# POWER_INPUT_STAGE.net
KiCad netlist of a schematic drawn in Altium Designer
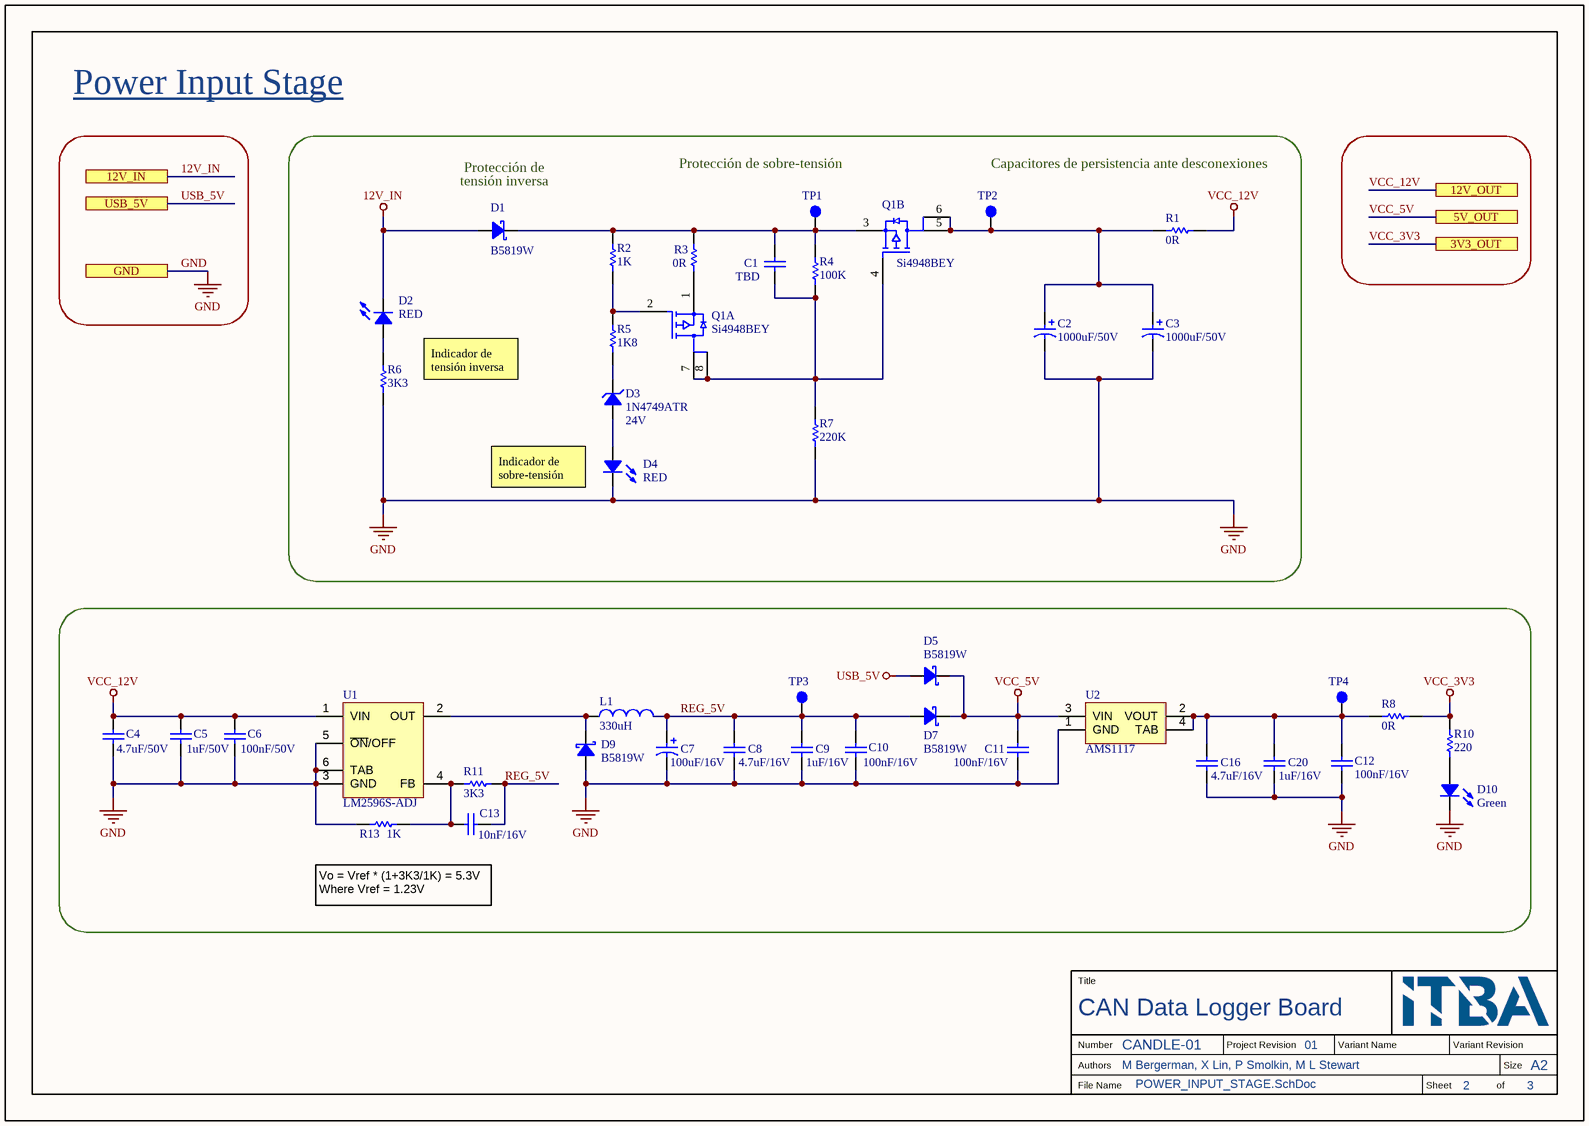
[diagram p0: POWER_INPUT_STAGE.SchDoc]

(export (version "E")
  (design (tool "Eeschema 10.0.6"))
  (components
    (comp (ref "C1")
      (value "TBD")
      (footprint "CAP0805")
      (description "SMD 0805 Capacitor")
      (libsource (lib "CANDLE-LIB") (part "Capacitor"))
    )
    (comp (ref "C2")
      (value "1000uF/50V")
      (footprint "RAD-CAP-12.5/5mm")
      (description "Polarized Capacitor (Radial)")
      (libsource (lib "CANDLE-LIB") (part "Capacitor Polarized"))
    )
    (comp (ref "C3")
      (value "1000uF/50V")
      (footprint "RAD-CAP-12.5/5mm")
      (description "Polarized Capacitor (Radial)")
      (libsource (lib "CANDLE-LIB") (part "Capacitor Polarized"))
    )
    (comp (ref "C4")
      (value "4.7uF/50V")
      (footprint "CAP0805")
      (description "SMD 0805 Capacitor")
      (libsource (lib "CANDLE-LIB") (part "Capacitor"))
    )
    (comp (ref "C5")
      (value "1uF/50V")
      (footprint "CAP0805")
      (description "SMD 0805 Capacitor")
      (libsource (lib "CANDLE-LIB") (part "Capacitor"))
    )
    (comp (ref "C6")
      (value "100nF/50V")
      (footprint "CAP0805")
      (description "SMD 0805 Capacitor")
      (libsource (lib "CANDLE-LIB") (part "Capacitor"))
    )
    (comp (ref "C7")
      (value "100uF/16V")
      (footprint "RAD-CAP-12.5/5mm")
      (description "Polarized Capacitor (Radial)")
      (libsource (lib "CANDLE-LIB") (part "Capacitor Polarized"))
    )
    (comp (ref "C8")
      (value "4.7uF/16V")
      (footprint "CAP0805")
      (description "SMD 0805 Capacitor")
      (libsource (lib "CANDLE-LIB") (part "Capacitor"))
    )
    (comp (ref "C9")
      (value "1uF/16V")
      (footprint "CAP0805")
      (description "SMD 0805 Capacitor")
      (libsource (lib "CANDLE-LIB") (part "Capacitor"))
    )
    (comp (ref "C10")
      (value "100nF/16V")
      (footprint "CAP0805")
      (description "SMD 0805 Capacitor")
      (libsource (lib "CANDLE-LIB") (part "Capacitor"))
    )
    (comp (ref "C11")
      (value "100nF/16V")
      (footprint "CAP0805")
      (description "SMD 0805 Capacitor")
      (libsource (lib "CANDLE-LIB") (part "Capacitor"))
    )
    (comp (ref "C12")
      (value "100nF/16V")
      (footprint "CAP0805")
      (description "SMD 0805 Capacitor")
      (libsource (lib "CANDLE-LIB") (part "Capacitor"))
    )
    (comp (ref "C13")
      (value "10nF/16V")
      (footprint "CAP0805")
      (description "SMD 0805 Capacitor")
      (libsource (lib "CANDLE-LIB") (part "Capacitor"))
    )
    (comp (ref "C16")
      (value "4.7uF/16V")
      (footprint "CAP0805")
      (description "SMD 0805 Capacitor")
      (libsource (lib "CANDLE-LIB") (part "Capacitor"))
    )
    (comp (ref "C20")
      (value "1uF/16V")
      (footprint "CAP0805")
      (description "SMD 0805 Capacitor")
      (libsource (lib "CANDLE-LIB") (part "Capacitor"))
    )
    (comp (ref "D1")
      (value "B5819W")
      (footprint "SOD-123")
      (description "Schottky Diode")
      (libsource (lib "CANDLE-LIB") (part "Diode Schottky"))
    )
    (comp (ref "D2")
      (value "RED")
      (footprint "LED-3MM-RED-RA")
      (description "Red 3mm LED")
      (libsource (lib "CANDLE-LIB") (part "LED 3mm Red RA"))
    )
    (comp (ref "D3")
      (value "1N4749ATR")
      (footprint "DO-35")
      (description "Zener Diode")
      (fields (field (name "VOLTAGE") "24V"))
      (libsource (lib "CANDLE-LIB") (part "Diode Zener"))
    )
    (comp (ref "D4")
      (value "RED")
      (footprint "LED-3MM-RED-RA")
      (description "Red 3mm LED")
      (libsource (lib "CANDLE-LIB") (part "LED 3mm Red RA"))
    )
    (comp (ref "D5")
      (value "B5819W")
      (footprint "SOD-123")
      (description "Schottky Diode")
      (libsource (lib "CANDLE-LIB") (part "Diode Schottky"))
    )
    (comp (ref "D7")
      (value "B5819W")
      (footprint "SOD-123")
      (description "Schottky Diode")
      (libsource (lib "CANDLE-LIB") (part "Diode Schottky"))
    )
    (comp (ref "D9")
      (value "B5819W")
      (footprint "SOD-123")
      (description "Schottky Diode")
      (libsource (lib "CANDLE-LIB") (part "Diode Schottky"))
    )
    (comp (ref "D10")
      (value "Green")
      (footprint "LED-3MM-GREEN-RA")
      (description "Green 3mm LED")
      (libsource (lib "CANDLE-LIB") (part "LED 3mm Green RA"))
    )
    (comp (ref "L1")
      (value "330uH")
      (footprint "DRQ127-INDUCTOR")
      (description "Inductor")
      (fields (field (name "PUBLISHER") "Altium Limited"))
      (libsource (lib "CANDLE-LIB") (part "Inductor"))
    )
    (comp (ref "Q1")
      (value "Si4948BEY")
      (footprint "8-SOIC")
      (description "MOSFET 2P-CH 60V 2.4A 8-SOIC")
      (libsource (lib "CANDLE-LIB") (part "Si4948BEY"))
    )
    (comp (ref "R1")
      (value "0R")
      (footprint "RES0805")
      (description "SMD 0805 Resistor")
      (libsource (lib "CANDLE-LIB") (part "Resistor"))
    )
    (comp (ref "R2")
      (value "1K")
      (footprint "RES0805")
      (description "SMD 0805 Resistor")
      (libsource (lib "CANDLE-LIB") (part "Resistor"))
    )
    (comp (ref "R3")
      (value "0R")
      (footprint "RES0805")
      (description "SMD 0805 Resistor")
      (libsource (lib "CANDLE-LIB") (part "Resistor"))
    )
    (comp (ref "R4")
      (value "100K")
      (footprint "RES0805")
      (description "SMD 0805 Resistor")
      (libsource (lib "CANDLE-LIB") (part "Resistor"))
    )
    (comp (ref "R5")
      (value "1K8")
      (footprint "RES0805")
      (description "SMD 0805 Resistor")
      (libsource (lib "CANDLE-LIB") (part "Resistor"))
    )
    (comp (ref "R6")
      (value "3K3")
      (footprint "RES0805")
      (description "SMD 0805 Resistor")
      (libsource (lib "CANDLE-LIB") (part "Resistor"))
    )
    (comp (ref "R7")
      (value "220K")
      (footprint "RES0805")
      (description "SMD 0805 Resistor")
      (libsource (lib "CANDLE-LIB") (part "Resistor"))
    )
    (comp (ref "R8")
      (value "0R")
      (footprint "RES0805")
      (description "SMD 0805 Resistor")
      (libsource (lib "CANDLE-LIB") (part "Resistor"))
    )
    (comp (ref "R10")
      (value "220")
      (footprint "RES0805")
      (description "SMD 0805 Resistor")
      (libsource (lib "CANDLE-LIB") (part "Resistor"))
    )
    (comp (ref "R11")
      (value "3K3")
      (footprint "RES0805")
      (description "SMD 0805 Resistor")
      (libsource (lib "CANDLE-LIB") (part "Resistor"))
    )
    (comp (ref "R13")
      (value "1K")
      (footprint "RES0805")
      (description "SMD 0805 Resistor")
      (libsource (lib "CANDLE-LIB") (part "Resistor"))
    )
    (comp (ref "TP1")
      (value "Testpoint")
      (footprint "TP_SMD_Ø1.0mm")
      (libsource (lib "CANDLE-LIB") (part "Testpoint"))
    )
    (comp (ref "TP2")
      (value "Testpoint")
      (footprint "TP_SMD_Ø1.0mm")
      (libsource (lib "CANDLE-LIB") (part "Testpoint"))
    )
    (comp (ref "TP3")
      (value "Testpoint")
      (footprint "TP_SMD_Ø1.0mm")
      (libsource (lib "CANDLE-LIB") (part "Testpoint"))
    )
    (comp (ref "TP4")
      (value "Testpoint")
      (footprint "TP_SMD_Ø1.0mm")
      (libsource (lib "CANDLE-LIB") (part "Testpoint"))
    )
    (comp (ref "U1")
      (value "LM2596S-ADJ")
      (footprint "LM2596S-ADJ/NOPB")
      (description "SIMPLE SWITCHER® Power Converter 150 KHz 3A Step-Down Voltage Regulator, 5-pin TO-263, Pb-Free")
      (libsource (lib "CANDLE-LIB") (part "LM2596S-ADJ/NOPB"))
    )
    (comp (ref "U2")
      (value "AMS1117")
      (footprint "SOT223")
      (description "1A LOW DROPOUT VOLTAGE REGULATOR")
      (libsource (lib "CANDLE-LIB") (part "AMS1117"))
    )
  )
  (nets
    (net (code "1") (name "/REG_5V") (class "Default")
      (node (ref "C10") (pin "2") (pinfunction "2_2") (pintype "passive"))
      (node (ref "C13") (pin "2") (pinfunction "2_2") (pintype "passive"))
      (node (ref "C7") (pin "2") (pinfunction "2_2") (pintype "passive"))
      (node (ref "C8") (pin "2") (pinfunction "2_2") (pintype "passive"))
      (node (ref "C9") (pin "2") (pinfunction "2_2") (pintype "passive"))
      (node (ref "D7") (pin "1") (pinfunction "A_1") (pintype "passive"))
      (node (ref "L1") (pin "2") (pinfunction "2_2") (pintype "passive"))
      (node (ref "R11") (pin "1") (pinfunction "1_1") (pintype "passive"))
      (node (ref "TP3") (pin "1") (pinfunction "TP_1") (pintype "passive"))
    )
    (net (code "2") (name "12V_IN") (class "Default")
      (node (ref "D1") (pin "1") (pinfunction "A_1") (pintype "passive"))
      (node (ref "D2") (pin "2") (pinfunction "K_2") (pintype "passive"))
    )
    (net (code "3") (name "GND") (class "Default")
      (node (ref "C10") (pin "1") (pinfunction "1_1") (pintype "passive"))
      (node (ref "C11") (pin "1") (pinfunction "1_1") (pintype "passive"))
      (node (ref "C12") (pin "1") (pinfunction "1_1") (pintype "passive"))
      (node (ref "C16") (pin "1") (pinfunction "1_1") (pintype "passive"))
      (node (ref "C2") (pin "1") (pinfunction "1_1") (pintype "passive"))
      (node (ref "C20") (pin "1") (pinfunction "1_1") (pintype "passive"))
      (node (ref "C3") (pin "1") (pinfunction "1_1") (pintype "passive"))
      (node (ref "C4") (pin "1") (pinfunction "1_1") (pintype "passive"))
      (node (ref "C5") (pin "1") (pinfunction "1_1") (pintype "passive"))
      (node (ref "C6") (pin "1") (pinfunction "1_1") (pintype "passive"))
      (node (ref "C7") (pin "1") (pinfunction "1_1") (pintype "passive"))
      (node (ref "C8") (pin "1") (pinfunction "1_1") (pintype "passive"))
      (node (ref "C9") (pin "1") (pinfunction "1_1") (pintype "passive"))
      (node (ref "D10") (pin "2") (pinfunction "K_2") (pintype "passive"))
      (node (ref "D4") (pin "2") (pinfunction "K_2") (pintype "passive"))
      (node (ref "D9") (pin "1") (pinfunction "A_1") (pintype "passive"))
      (node (ref "R13") (pin "2") (pinfunction "2_2") (pintype "passive"))
      (node (ref "R6") (pin "1") (pinfunction "1_1") (pintype "passive"))
      (node (ref "R7") (pin "1") (pinfunction "1_1") (pintype "passive"))
      (node (ref "U1") (pin "3") (pinfunction "GND_3") (pintype "power_in"))
      (node (ref "U1") (pin "5") (pinfunction "~{ON}/OFF_5") (pintype "passive"))
      (node (ref "U1") (pin "6") (pinfunction "TAB_6") (pintype "passive"))
      (node (ref "U2") (pin "1") (pinfunction "GND_1") (pintype "passive"))
    )
    (net (code "4") (name "Net-(D1-K)") (class "Default")
      (node (ref "C1") (pin "2") (pinfunction "2_2") (pintype "passive"))
      (node (ref "D1") (pin "2") (pinfunction "K_2") (pintype "passive"))
      (node (ref "Q1") (pin "3") (pinfunction "S2_3") (pintype "passive"))
      (node (ref "R2") (pin "2") (pinfunction "2_2") (pintype "passive"))
      (node (ref "R3") (pin "2") (pinfunction "2_2") (pintype "passive"))
      (node (ref "R4") (pin "2") (pinfunction "2_2") (pintype "passive"))
      (node (ref "TP1") (pin "1") (pinfunction "TP_1") (pintype "passive"))
    )
    (net (code "5") (name "Net-(D2-A)") (class "Default")
      (node (ref "D2") (pin "1") (pinfunction "A_1") (pintype "passive"))
      (node (ref "R6") (pin "2") (pinfunction "2_2") (pintype "passive"))
    )
    (net (code "6") (name "Net-(D3-A)") (class "Default")
      (node (ref "D3") (pin "2") (pinfunction "A_2") (pintype "passive"))
      (node (ref "D4") (pin "1") (pinfunction "A_1") (pintype "passive"))
    )
    (net (code "7") (name "Net-(D3-K)") (class "Default")
      (node (ref "D3") (pin "1") (pinfunction "K_1") (pintype "passive"))
      (node (ref "R5") (pin "1") (pinfunction "1_1") (pintype "passive"))
    )
    (net (code "8") (name "Net-(D9-K)") (class "Default")
      (node (ref "D9") (pin "2") (pinfunction "K_2") (pintype "passive"))
      (node (ref "L1") (pin "1") (pinfunction "1_1") (pintype "passive"))
      (node (ref "U1") (pin "2") (pinfunction "OUT_2") (pintype "power_in"))
    )
    (net (code "9") (name "Net-(D10-A)") (class "Default")
      (node (ref "D10") (pin "1") (pinfunction "A_1") (pintype "passive"))
      (node (ref "R10") (pin "2") (pinfunction "2_2") (pintype "passive"))
    )
    (net (code "10") (name "Net-(Q1A-G1)") (class "Default")
      (node (ref "Q1") (pin "2") (pinfunction "G1_2") (pintype "passive"))
      (node (ref "R2") (pin "1") (pinfunction "1_1") (pintype "passive"))
      (node (ref "R5") (pin "2") (pinfunction "2_2") (pintype "passive"))
    )
    (net (code "11") (name "Net-(Q1A-S1)") (class "Default")
      (node (ref "Q1") (pin "1") (pinfunction "S1_1") (pintype "passive"))
      (node (ref "R3") (pin "1") (pinfunction "1_1") (pintype "passive"))
    )
    (net (code "12") (name "Net-(Q1B-G2)") (class "Default")
      (node (ref "C1") (pin "1") (pinfunction "1_1") (pintype "passive"))
      (node (ref "Q1") (pin "4") (pinfunction "G2_4") (pintype "passive"))
      (node (ref "Q1") (pin "7") (pinfunction "D1_7") (pintype "passive"))
      (node (ref "Q1") (pin "8") (pinfunction "D1_8") (pintype "passive"))
      (node (ref "R4") (pin "1") (pinfunction "1_1") (pintype "passive"))
      (node (ref "R7") (pin "2") (pinfunction "2_2") (pintype "passive"))
    )
    (net (code "13") (name "Net-(TP2-TP)") (class "Default")
      (node (ref "C2") (pin "2") (pinfunction "2_2") (pintype "passive"))
      (node (ref "C3") (pin "2") (pinfunction "2_2") (pintype "passive"))
      (node (ref "Q1") (pin "5") (pinfunction "D2_5") (pintype "passive"))
      (node (ref "Q1") (pin "6") (pinfunction "D2_6") (pintype "passive"))
      (node (ref "R1") (pin "1") (pinfunction "1_1") (pintype "passive"))
      (node (ref "TP2") (pin "1") (pinfunction "TP_1") (pintype "passive"))
    )
    (net (code "14") (name "Net-(TP4-TP)") (class "Default")
      (node (ref "C12") (pin "2") (pinfunction "2_2") (pintype "passive"))
      (node (ref "C16") (pin "2") (pinfunction "2_2") (pintype "passive"))
      (node (ref "C20") (pin "2") (pinfunction "2_2") (pintype "passive"))
      (node (ref "R8") (pin "1") (pinfunction "1_1") (pintype "passive"))
      (node (ref "TP4") (pin "1") (pinfunction "TP_1") (pintype "passive"))
      (node (ref "U2") (pin "2") (pinfunction "VOUT_2") (pintype "power_in"))
      (node (ref "U2") (pin "4") (pinfunction "TAB_4") (pintype "power_in"))
    )
    (net (code "15") (name "Net-(U1-FB)") (class "Default")
      (node (ref "C13") (pin "1") (pinfunction "1_1") (pintype "passive"))
      (node (ref "R11") (pin "2") (pinfunction "2_2") (pintype "passive"))
      (node (ref "R13") (pin "1") (pinfunction "1_1") (pintype "passive"))
      (node (ref "U1") (pin "4") (pinfunction "FB_4") (pintype "passive"))
    )
    (net (code "16") (name "USB_5V") (class "Default")
      (node (ref "D5") (pin "1") (pinfunction "A_1") (pintype "passive"))
    )
    (net (code "17") (name "VCC_3V3") (class "Default")
      (node (ref "R10") (pin "1") (pinfunction "1_1") (pintype "passive"))
      (node (ref "R8") (pin "2") (pinfunction "2_2") (pintype "passive"))
    )
    (net (code "18") (name "VCC_5V") (class "Default")
      (node (ref "C11") (pin "2") (pinfunction "2_2") (pintype "passive"))
      (node (ref "D5") (pin "2") (pinfunction "K_2") (pintype "passive"))
      (node (ref "D7") (pin "2") (pinfunction "K_2") (pintype "passive"))
      (node (ref "U2") (pin "3") (pinfunction "VIN_3") (pintype "power_in"))
    )
    (net (code "19") (name "VCC_12V") (class "Default")
      (node (ref "C4") (pin "2") (pinfunction "2_2") (pintype "passive"))
      (node (ref "C5") (pin "2") (pinfunction "2_2") (pintype "passive"))
      (node (ref "C6") (pin "2") (pinfunction "2_2") (pintype "passive"))
      (node (ref "R1") (pin "2") (pinfunction "2_2") (pintype "passive"))
      (node (ref "U1") (pin "1") (pinfunction "VIN_1") (pintype "power_in"))
    )
  )
)
